# CC3000_WiFi_Shield.net
KiCad netlist of a schematic drawn in EAGLE
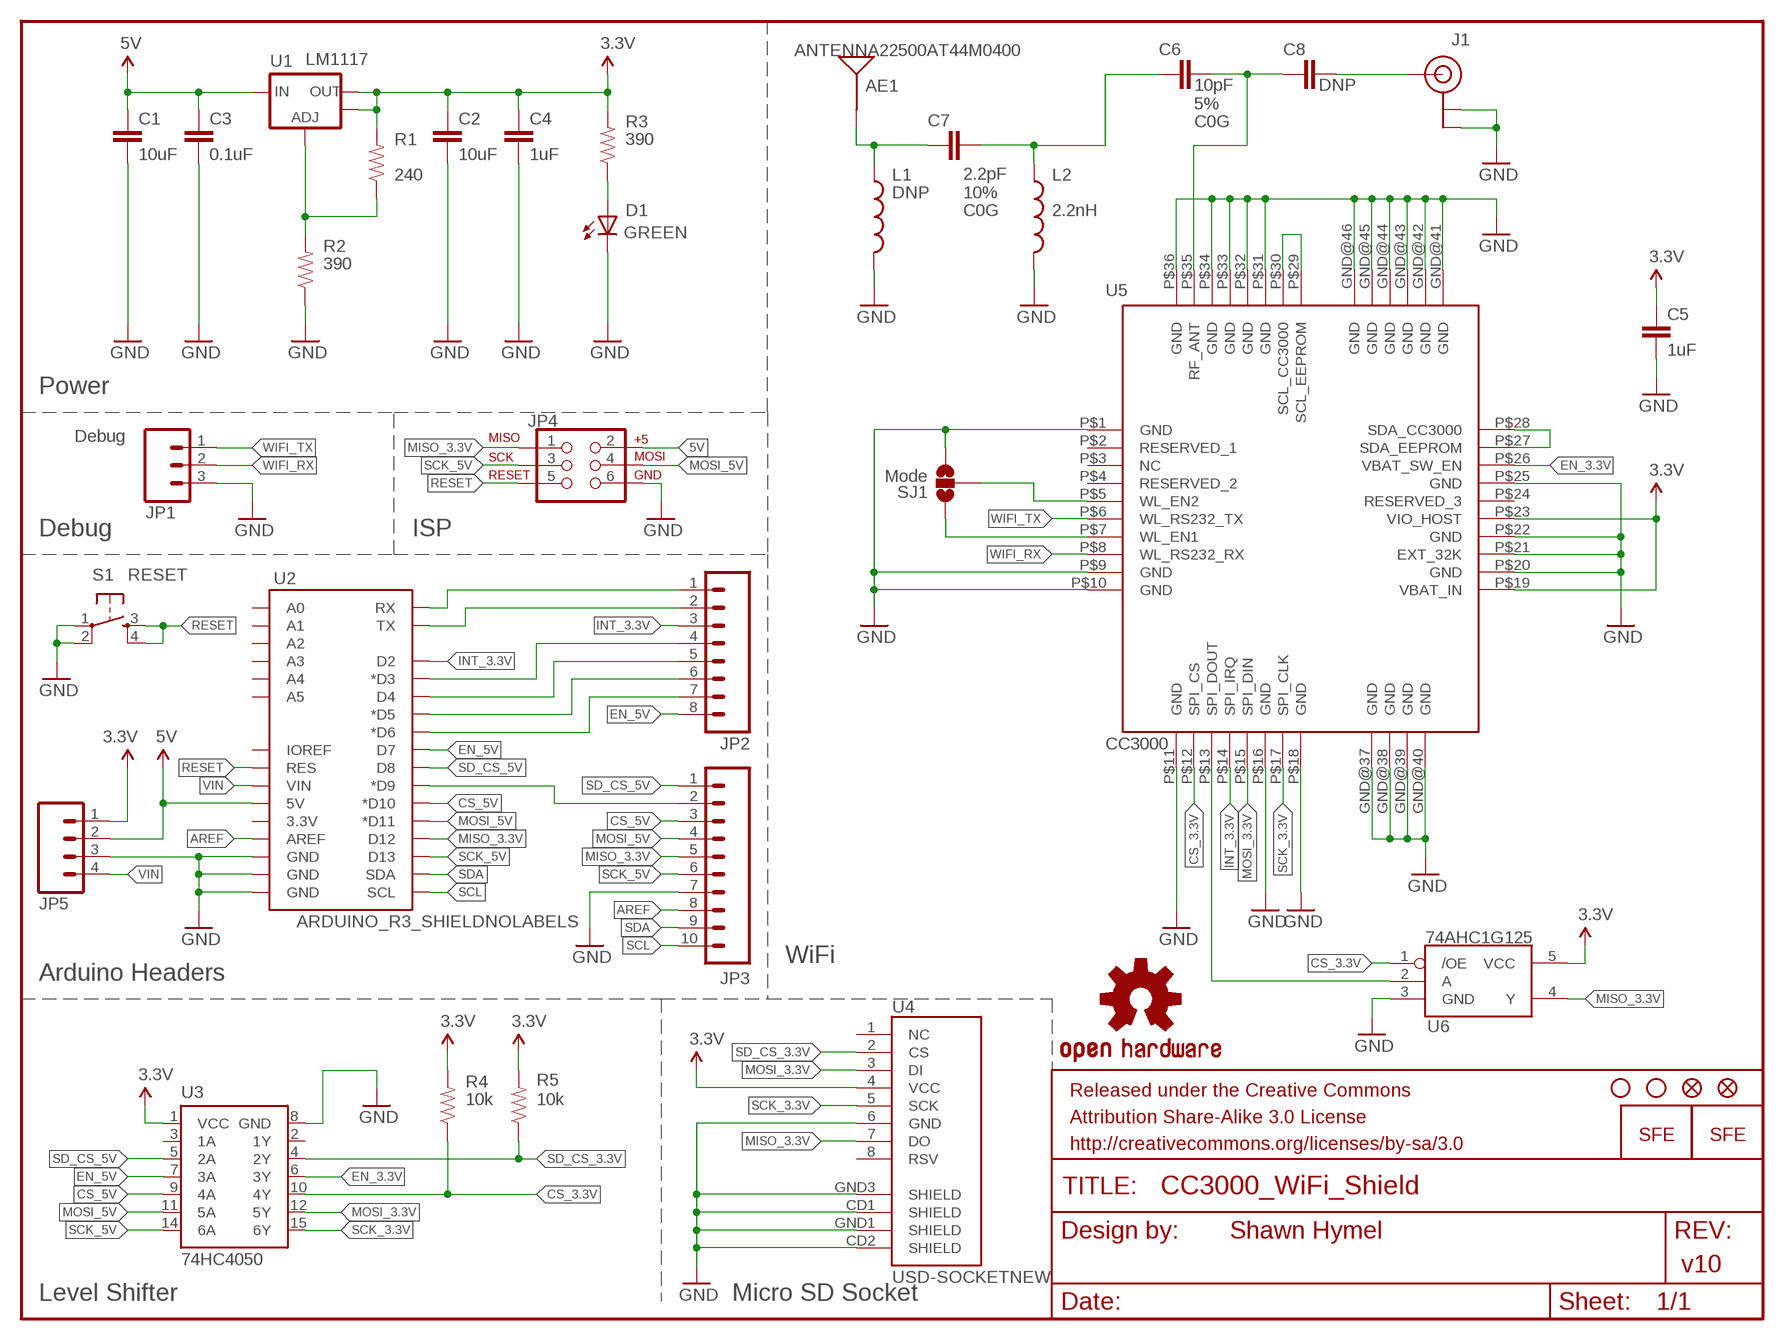
[diagram p0: schematic, sheet 1]

(export (version "E")
  (design (tool "Eeschema 10.0.6"))
  (components
    (comp (ref "AE1")
      (value "ANTENNA22500AT44M0400")
      (footprint "eagle-import:ANTENNA-CHIP_2500AT44M0400")
      (libsource (lib "eagle-import") (part "ANTENNA22500AT44M0400"))
    )
    (comp (ref "C1")
      (value "10uF")
      (footprint "eagle-import:0805")
      (libsource (lib "eagle-import") (part "CAP0805"))
    )
    (comp (ref "C2")
      (value "10uF")
      (footprint "eagle-import:0805")
      (libsource (lib "eagle-import") (part "CAP0805"))
    )
    (comp (ref "C3")
      (value "0.1uF")
      (footprint "eagle-import:0603-CAP")
      (libsource (lib "eagle-import") (part "CAP0603-CAP"))
    )
    (comp (ref "C4")
      (value "1uF")
      (footprint "eagle-import:0805")
      (libsource (lib "eagle-import") (part "CAP0805"))
    )
    (comp (ref "C5")
      (value "1uF")
      (footprint "eagle-import:0805")
      (libsource (lib "eagle-import") (part "CAP0805"))
    )
    (comp (ref "C6")
      (value "10pF")
      (footprint "eagle-import:0603-CAP")
      (fields (field (name "COEFF") "C0G") (field (name "TOL") "5%"))
      (libsource (lib "eagle-import") (part "CAP0603-CAP"))
    )
    (comp (ref "C7")
      (value "2.2pF")
      (footprint "eagle-import:0603-CAP")
      (fields (field (name "COEFF") "C0G") (field (name "TOL") "10%"))
      (libsource (lib "eagle-import") (part "CAP0603-CAP"))
    )
    (comp (ref "C8")
      (value "DNP")
      (footprint "eagle-import:0603-CAP")
      (libsource (lib "eagle-import") (part "CAP0603-CAP"))
    )
    (comp (ref "D1")
      (value "GREEN")
      (footprint "eagle-import:LED-0603")
      (libsource (lib "eagle-import") (part "LED-GREEN0603"))
    )
    (comp (ref "FID1")
      (value "FIDUCIAL1X2")
      (footprint "eagle-import:FIDUCIAL-1X2")
      (libsource (lib "eagle-import") (part "FIDUCIAL1X2"))
    )
    (comp (ref "FID2")
      (value "FIDUCIAL1X2")
      (footprint "eagle-import:FIDUCIAL-1X2")
      (libsource (lib "eagle-import") (part "FIDUCIAL1X2"))
    )
    (comp (ref "FRAME1")
      (value "FRAME-LETTER")
      (footprint "eagle-import:CREATIVE_COMMONS")
      (libsource (lib "eagle-import") (part "FRAME-LETTER"))
    )
    (comp (ref "J1")
      (value "U.FL")
      (footprint "eagle-import:U.FL")
      (libsource (lib "eagle-import") (part "U.FL"))
    )
    (comp (ref "JP1")
      (value "Debug")
      (footprint "eagle-import:1X03")
      (libsource (lib "eagle-import") (part "M03PTH"))
    )
    (comp (ref "JP2")
      (value "M08NO_SILK")
      (footprint "eagle-import:1X08_NO_SILK")
      (libsource (lib "eagle-import") (part "M08NO_SILK"))
    )
    (comp (ref "JP3")
      (value "M10NO_SILK")
      (footprint "eagle-import:1X10_NO_SILK")
      (libsource (lib "eagle-import") (part "M10NO_SILK"))
    )
    (comp (ref "JP4")
      (value "AVR_SPI_PRG_6PTH")
      (footprint "eagle-import:2X3")
      (libsource (lib "eagle-import") (part "AVR_SPI_PRG_6PTH"))
    )
    (comp (ref "JP5")
      (value "M04PTH")
      (footprint "eagle-import:1X04")
      (libsource (lib "eagle-import") (part "M04PTH"))
    )
    (comp (ref "L1")
      (value "DNP")
      (footprint "eagle-import:0603")
      (libsource (lib "eagle-import") (part "INDUCTOR0603"))
    )
    (comp (ref "L2")
      (value "2.2nH")
      (footprint "eagle-import:0603")
      (libsource (lib "eagle-import") (part "INDUCTOR0603"))
    )
    (comp (ref "LOGO1")
      (value "OSHW-LOGOS")
      (footprint "eagle-import:OSHW-LOGO-S")
      (libsource (lib "eagle-import") (part "OSHW-LOGOS"))
    )
    (comp (ref "LOGO2")
      (value "LOGO-SFENEW")
      (footprint "eagle-import:SFE-NEW-WEBLOGO")
      (libsource (lib "eagle-import") (part "LOGO-SFENEW"))
    )
    (comp (ref "LOGO3")
      (value "LOGO-SFESK")
      (footprint "eagle-import:SFE-LOGO-FLAME")
      (libsource (lib "eagle-import") (part "LOGO-SFESK"))
    )
    (comp (ref "R1")
      (value "240")
      (footprint "eagle-import:0603-RES")
      (libsource (lib "eagle-import") (part "RESISTOR0603"))
    )
    (comp (ref "R2")
      (value "390")
      (footprint "eagle-import:0603-RES")
      (libsource (lib "eagle-import") (part "RESISTOR0603"))
    )
    (comp (ref "R3")
      (value "390")
      (footprint "eagle-import:0603-RES")
      (libsource (lib "eagle-import") (part "RESISTOR0603-RES"))
    )
    (comp (ref "R4")
      (value "10k")
      (footprint "eagle-import:0603-RES")
      (libsource (lib "eagle-import") (part "RESISTOR0603-RES"))
    )
    (comp (ref "R5")
      (value "10k")
      (footprint "eagle-import:0603-RES")
      (libsource (lib "eagle-import") (part "RESISTOR0603-RES"))
    )
    (comp (ref "S1")
      (value "RESET")
      (footprint "eagle-import:TACTILE_SWITCH_SMD")
      (libsource (lib "eagle-import") (part "TAC_SWITCHSMD"))
    )
    (comp (ref "SJ1")
      (value "Mode")
      (footprint "eagle-import:SJ_3_PASTE1&2")
      (libsource (lib "eagle-import") (part "SOLDERJUMPER_2WAYPASTE1&2"))
    )
    (comp (ref "STANDOFF1")
      (value "STAND-OFF")
      (footprint "eagle-import:STAND-OFF")
      (libsource (lib "eagle-import") (part "STAND-OFF"))
    )
    (comp (ref "STANDOFF2")
      (value "STAND-OFF")
      (footprint "eagle-import:STAND-OFF")
      (libsource (lib "eagle-import") (part "STAND-OFF"))
    )
    (comp (ref "U1")
      (value "LM1117")
      (footprint "eagle-import:SOT223")
      (libsource (lib "eagle-import") (part "V_REG_LM1117SOT223"))
    )
    (comp (ref "U2")
      (value "ARDUINO_R3_SHIELDNOLABELS")
      (footprint "eagle-import:UNO_R3_SHIELD_NOLABELS")
      (libsource (lib "eagle-import") (part "ARDUINO_R3_SHIELDNOLABELS"))
    )
    (comp (ref "U3")
      (value "74HC4050")
      (footprint "eagle-import:SO016")
      (libsource (lib "eagle-import") (part "HEX_CONVERTER"))
    )
    (comp (ref "U4")
      (value "USD-SOCKETNEW")
      (footprint "eagle-import:MICRO-SD-SOCKET-PP")
      (libsource (lib "eagle-import") (part "USD-SOCKETNEW"))
    )
    (comp (ref "U5")
      (value "CC3000")
      (footprint "eagle-import:QFN-46_CC3000")
      (libsource (lib "eagle-import") (part "CC3000"))
    )
    (comp (ref "U6")
      (value "74AHC1G125")
      (footprint "eagle-import:SOT23-5")
      (libsource (lib "eagle-import") (part "74AHC1G125"))
    )
  )
  (nets
    (net (code "1") (name "3.3V") (class "Default")
      (node (ref "C2") (pin "1") (pinfunction "1_1") (pintype "passive"))
      (node (ref "C4") (pin "1") (pinfunction "1_1") (pintype "passive"))
      (node (ref "C5") (pin "1") (pinfunction "1_1") (pintype "passive"))
      (node (ref "JP5") (pin "1") (pinfunction "1_1") (pintype "passive"))
      (node (ref "R1") (pin "2") (pinfunction "2_2") (pintype "passive"))
      (node (ref "R3") (pin "2") (pinfunction "2_2") (pintype "passive"))
      (node (ref "R4") (pin "2") (pinfunction "2_2") (pintype "passive"))
      (node (ref "R5") (pin "2") (pinfunction "2_2") (pintype "passive"))
      (node (ref "U1") (pin "2") (pinfunction "OUT_2") (pintype "output"))
      (node (ref "U1") (pin "4") (pinfunction "OUT_4") (pintype "output"))
      (node (ref "U3") (pin "1") (pinfunction "VCC_1") (pintype "bidirectional"))
      (node (ref "U4") (pin "4") (pinfunction "VCC_4") (pintype "bidirectional"))
      (node (ref "U5") (pin "P$19") (pinfunction "VBAT_IN_P$19") (pintype "bidirectional"))
      (node (ref "U5") (pin "P$23") (pinfunction "VIO_HOST_P$23") (pintype "bidirectional"))
      (node (ref "U6") (pin "5") (pinfunction "VCC_5") (pintype "bidirectional"))
    )
    (net (code "2") (name "5V") (class "Default")
      (node (ref "C1") (pin "1") (pinfunction "1_1") (pintype "passive"))
      (node (ref "C3") (pin "1") (pinfunction "1_1") (pintype "passive"))
      (node (ref "JP4") (pin "2") (pinfunction "2_2") (pintype "passive"))
      (node (ref "JP5") (pin "2") (pinfunction "2_2") (pintype "passive"))
      (node (ref "U1") (pin "3") (pinfunction "IN_3") (pintype "input"))
      (node (ref "U2") (pin "5V") (pinfunction "5V_5V") (pintype "bidirectional"))
    )
    (net (code "3") (name "AREF") (class "Default")
      (node (ref "JP3") (pin "8") (pinfunction "8_8") (pintype "passive"))
      (node (ref "U2") (pin "AREF") (pinfunction "AREF_AREF") (pintype "bidirectional"))
    )
    (net (code "4") (name "CS_3.3V") (class "Default")
      (node (ref "R4") (pin "1") (pinfunction "1_1") (pintype "passive"))
      (node (ref "U3") (pin "10") (pinfunction "4Y_10") (pintype "bidirectional"))
      (node (ref "U5") (pin "P$12") (pinfunction "SPI_CS_P$12") (pintype "bidirectional"))
      (node (ref "U6") (pin "1") (pinfunction "/OE_1") (pintype "bidirectional"))
    )
    (net (code "5") (name "CS_5V") (class "Default")
      (node (ref "JP3") (pin "3") (pinfunction "3_3") (pintype "passive"))
      (node (ref "U2") (pin "D10") (pinfunction "*D10_D10") (pintype "bidirectional"))
      (node (ref "U3") (pin "9") (pinfunction "4A_9") (pintype "bidirectional"))
    )
    (net (code "6") (name "EN_3.3V") (class "Default")
      (node (ref "U3") (pin "6") (pinfunction "3Y_6") (pintype "bidirectional"))
      (node (ref "U5") (pin "P$26") (pinfunction "VBAT_SW_EN_P$26") (pintype "bidirectional"))
    )
    (net (code "7") (name "EN_5V") (class "Default")
      (node (ref "JP2") (pin "8") (pinfunction "8_8") (pintype "passive"))
      (node (ref "U2") (pin "D7") (pinfunction "D7_D7") (pintype "bidirectional"))
      (node (ref "U3") (pin "7") (pinfunction "3A_7") (pintype "bidirectional"))
    )
    (net (code "8") (name "GND") (class "Default")
      (node (ref "C1") (pin "2") (pinfunction "2_2") (pintype "passive"))
      (node (ref "C2") (pin "2") (pinfunction "2_2") (pintype "passive"))
      (node (ref "C3") (pin "2") (pinfunction "2_2") (pintype "passive"))
      (node (ref "C4") (pin "2") (pinfunction "2_2") (pintype "passive"))
      (node (ref "C5") (pin "2") (pinfunction "2_2") (pintype "passive"))
      (node (ref "D1") (pin "C") (pinfunction "C_C") (pintype "passive"))
      (node (ref "J1") (pin "P$1") (pinfunction "GND_P$1") (pintype "bidirectional"))
      (node (ref "J1") (pin "P$2") (pinfunction "GND_P$2") (pintype "bidirectional"))
      (node (ref "JP1") (pin "3") (pinfunction "3_3") (pintype "passive"))
      (node (ref "JP3") (pin "7") (pinfunction "7_7") (pintype "passive"))
      (node (ref "JP4") (pin "6") (pinfunction "6_6") (pintype "passive"))
      (node (ref "JP5") (pin "3") (pinfunction "3_3") (pintype "passive"))
      (node (ref "L1") (pin "2") (pinfunction "2_2") (pintype "passive"))
      (node (ref "L2") (pin "2") (pinfunction "2_2") (pintype "passive"))
      (node (ref "R2") (pin "1") (pinfunction "1_1") (pintype "passive"))
      (node (ref "S1") (pin "1") (pinfunction "1_1") (pintype "passive"))
      (node (ref "S1") (pin "2") (pinfunction "2_2") (pintype "passive"))
      (node (ref "SJ1") (pin "3") (pinfunction "3_3") (pintype "passive"))
      (node (ref "U2") (pin "GND@0") (pinfunction "GND_GND@0") (pintype "bidirectional"))
      (node (ref "U2") (pin "GND@1") (pinfunction "GND_GND@1") (pintype "bidirectional"))
      (node (ref "U2") (pin "GND@2") (pinfunction "GND_GND@2") (pintype "bidirectional"))
      (node (ref "U3") (pin "8") (pinfunction "GND_8") (pintype "bidirectional"))
      (node (ref "U4") (pin "6") (pinfunction "GND_6") (pintype "bidirectional"))
      (node (ref "U4") (pin "CD1") (pinfunction "SHIELD_CD1") (pintype "bidirectional"))
      (node (ref "U4") (pin "CD2") (pinfunction "SHIELD_CD2") (pintype "bidirectional"))
      (node (ref "U4") (pin "GND1") (pinfunction "SHIELD_GND1") (pintype "bidirectional"))
      (node (ref "U4") (pin "GND3") (pinfunction "SHIELD_GND3") (pintype "bidirectional"))
      (node (ref "U5") (pin "GND@37") (pinfunction "GND_GND@37") (pintype "bidirectional"))
      (node (ref "U5") (pin "GND@38") (pinfunction "GND_GND@38") (pintype "bidirectional"))
      (node (ref "U5") (pin "GND@39") (pinfunction "GND_GND@39") (pintype "bidirectional"))
      (node (ref "U5") (pin "GND@40") (pinfunction "GND_GND@40") (pintype "bidirectional"))
      (node (ref "U5") (pin "GND@41") (pinfunction "GND_GND@41") (pintype "bidirectional"))
      (node (ref "U5") (pin "GND@42") (pinfunction "GND_GND@42") (pintype "bidirectional"))
      (node (ref "U5") (pin "GND@43") (pinfunction "GND_GND@43") (pintype "bidirectional"))
      (node (ref "U5") (pin "GND@44") (pinfunction "GND_GND@44") (pintype "bidirectional"))
      (node (ref "U5") (pin "GND@45") (pinfunction "GND_GND@45") (pintype "bidirectional"))
      (node (ref "U5") (pin "GND@46") (pinfunction "GND_GND@46") (pintype "bidirectional"))
      (node (ref "U5") (pin "P$1") (pinfunction "GND_P$1") (pintype "bidirectional"))
      (node (ref "U5") (pin "P$10") (pinfunction "GND_P$10") (pintype "bidirectional"))
      (node (ref "U5") (pin "P$11") (pinfunction "GND_P$11") (pintype "bidirectional"))
      (node (ref "U5") (pin "P$16") (pinfunction "GND_P$16") (pintype "bidirectional"))
      (node (ref "U5") (pin "P$18") (pinfunction "GND_P$18") (pintype "bidirectional"))
      (node (ref "U5") (pin "P$20") (pinfunction "GND_P$20") (pintype "bidirectional"))
      (node (ref "U5") (pin "P$21") (pinfunction "EXT_32K_P$21") (pintype "bidirectional"))
      (node (ref "U5") (pin "P$22") (pinfunction "GND_P$22") (pintype "bidirectional"))
      (node (ref "U5") (pin "P$25") (pinfunction "GND_P$25") (pintype "bidirectional"))
      (node (ref "U5") (pin "P$31") (pinfunction "GND_P$31") (pintype "bidirectional"))
      (node (ref "U5") (pin "P$32") (pinfunction "GND_P$32") (pintype "bidirectional"))
      (node (ref "U5") (pin "P$33") (pinfunction "GND_P$33") (pintype "bidirectional"))
      (node (ref "U5") (pin "P$34") (pinfunction "GND_P$34") (pintype "bidirectional"))
      (node (ref "U5") (pin "P$36") (pinfunction "GND_P$36") (pintype "bidirectional"))
      (node (ref "U5") (pin "P$9") (pinfunction "GND_P$9") (pintype "bidirectional"))
      (node (ref "U6") (pin "3") (pinfunction "GND_3") (pintype "bidirectional"))
    )
    (net (code "9") (name "INT_3.3V") (class "Default")
      (node (ref "JP2") (pin "3") (pinfunction "3_3") (pintype "passive"))
      (node (ref "U2") (pin "D2") (pinfunction "D2_D2") (pintype "bidirectional"))
      (node (ref "U5") (pin "P$14") (pinfunction "SPI_IRQ_P$14") (pintype "bidirectional"))
    )
    (net (code "10") (name "MISO_3.3V") (class "Default")
      (node (ref "JP3") (pin "5") (pinfunction "5_5") (pintype "passive"))
      (node (ref "JP4") (pin "1") (pinfunction "1_1") (pintype "passive"))
      (node (ref "U2") (pin "D12") (pinfunction "D12_D12") (pintype "bidirectional"))
      (node (ref "U4") (pin "7") (pinfunction "DO_7") (pintype "bidirectional"))
      (node (ref "U6") (pin "4") (pinfunction "Y_4") (pintype "bidirectional"))
    )
    (net (code "11") (name "MOSI_3.3V") (class "Default")
      (node (ref "U3") (pin "12") (pinfunction "5Y_12") (pintype "bidirectional"))
      (node (ref "U4") (pin "3") (pinfunction "DI_3") (pintype "bidirectional"))
      (node (ref "U5") (pin "P$15") (pinfunction "SPI_DIN_P$15") (pintype "bidirectional"))
    )
    (net (code "12") (name "MOSI_5V") (class "Default")
      (node (ref "JP3") (pin "4") (pinfunction "4_4") (pintype "passive"))
      (node (ref "JP4") (pin "4") (pinfunction "4_4") (pintype "passive"))
      (node (ref "U2") (pin "D11") (pinfunction "*D11_D11") (pintype "bidirectional"))
      (node (ref "U3") (pin "11") (pinfunction "5A_11") (pintype "bidirectional"))
    )
    (net (code "13") (name "Net-(AE1-SIGNAL)") (class "Default")
      (node (ref "AE1") (pin "FEED") (pinfunction "SIGNAL_FEED") (pintype "bidirectional"))
      (node (ref "C7") (pin "1") (pinfunction "1_1") (pintype "passive"))
      (node (ref "L1") (pin "1") (pinfunction "1_1") (pintype "passive"))
    )
    (net (code "14") (name "Net-(C6-Pad1)") (class "Default")
      (node (ref "C6") (pin "1") (pinfunction "1_1") (pintype "passive"))
      (node (ref "C7") (pin "2") (pinfunction "2_2") (pintype "passive"))
      (node (ref "L2") (pin "1") (pinfunction "1_1") (pintype "passive"))
    )
    (net (code "15") (name "Net-(D1-PadA)") (class "Default")
      (node (ref "D1") (pin "A") (pinfunction "A_A") (pintype "passive"))
      (node (ref "R3") (pin "1") (pinfunction "1_1") (pintype "passive"))
    )
    (net (code "16") (name "Net-(J1-SIGNAL)") (class "Default")
      (node (ref "C8") (pin "2") (pinfunction "2_2") (pintype "passive"))
      (node (ref "J1") (pin "P$3") (pinfunction "SIGNAL_P$3") (pintype "bidirectional"))
    )
    (net (code "17") (name "Net-(JP2-Pad1)") (class "Default")
      (node (ref "JP2") (pin "1") (pinfunction "1_1") (pintype "passive"))
      (node (ref "U2") (pin "RX") (pinfunction "RX_RX") (pintype "bidirectional"))
    )
    (net (code "18") (name "Net-(JP2-Pad2)") (class "Default")
      (node (ref "JP2") (pin "2") (pinfunction "2_2") (pintype "passive"))
      (node (ref "U2") (pin "TX") (pinfunction "TX_TX") (pintype "bidirectional"))
    )
    (net (code "19") (name "Net-(JP2-Pad5)") (class "Default")
      (node (ref "JP2") (pin "5") (pinfunction "5_5") (pintype "passive"))
      (node (ref "U2") (pin "D4") (pinfunction "D4_D4") (pintype "bidirectional"))
    )
    (net (code "20") (name "Net-(U1-ADJ)") (class "Default")
      (node (ref "R1") (pin "1") (pinfunction "1_1") (pintype "passive"))
      (node (ref "R2") (pin "2") (pinfunction "2_2") (pintype "passive"))
      (node (ref "U1") (pin "1") (pinfunction "ADJ_1") (pintype "input"))
    )
    (net (code "21") (name "Net-(U2-*D3)") (class "Default")
      (node (ref "JP2") (pin "4") (pinfunction "4_4") (pintype "passive"))
      (node (ref "U2") (pin "D3") (pinfunction "*D3_D3") (pintype "bidirectional"))
    )
    (net (code "22") (name "Net-(U2-*D5)") (class "Default")
      (node (ref "JP2") (pin "6") (pinfunction "6_6") (pintype "passive"))
      (node (ref "U2") (pin "D5") (pinfunction "*D5_D5") (pintype "bidirectional"))
    )
    (net (code "23") (name "Net-(U2-*D6)") (class "Default")
      (node (ref "JP2") (pin "7") (pinfunction "7_7") (pintype "passive"))
      (node (ref "U2") (pin "D6") (pinfunction "*D6_D6") (pintype "bidirectional"))
    )
    (net (code "24") (name "Net-(U2-*D9)") (class "Default")
      (node (ref "JP3") (pin "2") (pinfunction "2_2") (pintype "passive"))
      (node (ref "U2") (pin "D9") (pinfunction "*D9_D9") (pintype "bidirectional"))
    )
    (net (code "25") (name "Net-(U5-RF_ANT)") (class "Default")
      (node (ref "C6") (pin "2") (pinfunction "2_2") (pintype "passive"))
      (node (ref "C8") (pin "1") (pinfunction "1_1") (pintype "passive"))
      (node (ref "U5") (pin "P$35") (pinfunction "RF_ANT_P$35") (pintype "bidirectional"))
    )
    (net (code "26") (name "Net-(U5-SCL_CC3000)") (class "Default")
      (node (ref "U5") (pin "P$29") (pinfunction "SCL_EEPROM_P$29") (pintype "bidirectional"))
      (node (ref "U5") (pin "P$30") (pinfunction "SCL_CC3000_P$30") (pintype "bidirectional"))
    )
    (net (code "27") (name "Net-(U5-SDA_CC3000)") (class "Default")
      (node (ref "U5") (pin "P$27") (pinfunction "SDA_EEPROM_P$27") (pintype "bidirectional"))
      (node (ref "U5") (pin "P$28") (pinfunction "SDA_CC3000_P$28") (pintype "bidirectional"))
    )
    (net (code "28") (name "Net-(U5-SPI_DOUT)") (class "Default")
      (node (ref "U5") (pin "P$13") (pinfunction "SPI_DOUT_P$13") (pintype "bidirectional"))
      (node (ref "U6") (pin "2") (pinfunction "A_2") (pintype "bidirectional"))
    )
    (net (code "29") (name "Net-(U5-WL_EN1)") (class "Default")
      (node (ref "SJ1") (pin "1") (pinfunction "1_1") (pintype "passive"))
      (node (ref "U5") (pin "P$7") (pinfunction "WL_EN1_P$7") (pintype "bidirectional"))
    )
    (net (code "30") (name "Net-(U5-WL_EN2)") (class "Default")
      (node (ref "SJ1") (pin "2") (pinfunction "2_2") (pintype "passive"))
      (node (ref "U5") (pin "P$5") (pinfunction "WL_EN2_P$5") (pintype "bidirectional"))
    )
    (net (code "31") (name "RESET") (class "Default")
      (node (ref "JP4") (pin "5") (pinfunction "5_5") (pintype "passive"))
      (node (ref "S1") (pin "3") (pinfunction "3_3") (pintype "passive"))
      (node (ref "S1") (pin "4") (pinfunction "4_4") (pintype "passive"))
      (node (ref "U2") (pin "RES") (pinfunction "RES_RES") (pintype "bidirectional"))
    )
    (net (code "32") (name "SCK_3.3V") (class "Default")
      (node (ref "U3") (pin "15") (pinfunction "6Y_15") (pintype "bidirectional"))
      (node (ref "U4") (pin "5") (pinfunction "SCK_5") (pintype "bidirectional"))
      (node (ref "U5") (pin "P$17") (pinfunction "SPI_CLK_P$17") (pintype "bidirectional"))
    )
    (net (code "33") (name "SCK_5V") (class "Default")
      (node (ref "JP3") (pin "6") (pinfunction "6_6") (pintype "passive"))
      (node (ref "JP4") (pin "3") (pinfunction "3_3") (pintype "passive"))
      (node (ref "U2") (pin "D13") (pinfunction "D13_D13") (pintype "bidirectional"))
      (node (ref "U3") (pin "14") (pinfunction "6A_14") (pintype "bidirectional"))
    )
    (net (code "34") (name "SCL") (class "Default")
      (node (ref "JP3") (pin "10") (pinfunction "10_10") (pintype "passive"))
      (node (ref "U2") (pin "SCL") (pinfunction "SCL_SCL") (pintype "bidirectional"))
    )
    (net (code "35") (name "SDA") (class "Default")
      (node (ref "JP3") (pin "9") (pinfunction "9_9") (pintype "passive"))
      (node (ref "U2") (pin "SDA") (pinfunction "SDA_SDA") (pintype "bidirectional"))
    )
    (net (code "36") (name "SD_CS_3.3V") (class "Default")
      (node (ref "R5") (pin "1") (pinfunction "1_1") (pintype "passive"))
      (node (ref "U3") (pin "4") (pinfunction "2Y_4") (pintype "bidirectional"))
      (node (ref "U4") (pin "2") (pinfunction "CS_2") (pintype "bidirectional"))
    )
    (net (code "37") (name "SD_CS_5V") (class "Default")
      (node (ref "JP3") (pin "1") (pinfunction "1_1") (pintype "passive"))
      (node (ref "U2") (pin "D8") (pinfunction "D8_D8") (pintype "bidirectional"))
      (node (ref "U3") (pin "5") (pinfunction "2A_5") (pintype "bidirectional"))
    )
    (net (code "38") (name "VIN") (class "Default")
      (node (ref "JP5") (pin "4") (pinfunction "4_4") (pintype "passive"))
      (node (ref "U2") (pin "VIN") (pinfunction "VIN_VIN") (pintype "bidirectional"))
    )
    (net (code "39") (name "WIFI_RX") (class "Default")
      (node (ref "JP1") (pin "2") (pinfunction "2_2") (pintype "passive"))
      (node (ref "U5") (pin "P$8") (pinfunction "WL_RS232_RX_P$8") (pintype "bidirectional"))
    )
    (net (code "40") (name "WIFI_TX") (class "Default")
      (node (ref "JP1") (pin "1") (pinfunction "1_1") (pintype "passive"))
      (node (ref "U5") (pin "P$6") (pinfunction "WL_RS232_TX_P$6") (pintype "bidirectional"))
    )
    (net (code "41") (name "unconnected-(U2-Pad3.3V)") (class "Default")
      (node (ref "U2") (pin "3.3V") (pinfunction "3.3V_3.3V") (pintype "bidirectional"))
    )
    (net (code "42") (name "unconnected-(U2-PadA0)") (class "Default")
      (node (ref "U2") (pin "A0") (pinfunction "A0_A0") (pintype "bidirectional"))
    )
    (net (code "43") (name "unconnected-(U2-PadA1)") (class "Default")
      (node (ref "U2") (pin "A1") (pinfunction "A1_A1") (pintype "bidirectional"))
    )
    (net (code "44") (name "unconnected-(U2-PadA2)") (class "Default")
      (node (ref "U2") (pin "A2") (pinfunction "A2_A2") (pintype "bidirectional"))
    )
    (net (code "45") (name "unconnected-(U2-PadA3)") (class "Default")
      (node (ref "U2") (pin "A3") (pinfunction "A3_A3") (pintype "bidirectional"))
    )
    (net (code "46") (name "unconnected-(U2-PadA4)") (class "Default")
      (node (ref "U2") (pin "A4") (pinfunction "A4_A4") (pintype "bidirectional"))
    )
    (net (code "47") (name "unconnected-(U2-PadA5)") (class "Default")
      (node (ref "U2") (pin "A5") (pinfunction "A5_A5") (pintype "bidirectional"))
    )
    (net (code "48") (name "unconnected-(U2-PadIOREF)") (class "Default")
      (node (ref "U2") (pin "IOREF") (pinfunction "IOREF_IOREF") (pintype "bidirectional"))
    )
    (net (code "49") (name "unconnected-(U3-1A-Pad3)") (class "Default")
      (node (ref "U3") (pin "3") (pinfunction "1A_3") (pintype "bidirectional"))
    )
    (net (code "50") (name "unconnected-(U3-1Y-Pad2)") (class "Default")
      (node (ref "U3") (pin "2") (pinfunction "1Y_2") (pintype "bidirectional"))
    )
    (net (code "51") (name "unconnected-(U4-NC-Pad1)") (class "Default")
      (node (ref "U4") (pin "1") (pinfunction "NC_1") (pintype "bidirectional"))
    )
    (net (code "52") (name "unconnected-(U4-RSV-Pad8)") (class "Default")
      (node (ref "U4") (pin "8") (pinfunction "RSV_8") (pintype "bidirectional"))
    )
    (net (code "53") (name "unconnected-(U5-NC-PadP$3)") (class "Default")
      (node (ref "U5") (pin "P$3") (pinfunction "NC_P$3") (pintype "bidirectional"))
    )
    (net (code "54") (name "unconnected-(U5-RESERVED_1-PadP$2)") (class "Default")
      (node (ref "U5") (pin "P$2") (pinfunction "RESERVED_1_P$2") (pintype "bidirectional"))
    )
    (net (code "55") (name "unconnected-(U5-RESERVED_2-PadP$4)") (class "Default")
      (node (ref "U5") (pin "P$4") (pinfunction "RESERVED_2_P$4") (pintype "bidirectional"))
    )
    (net (code "56") (name "unconnected-(U5-RESERVED_3-PadP$24)") (class "Default")
      (node (ref "U5") (pin "P$24") (pinfunction "RESERVED_3_P$24") (pintype "bidirectional"))
    )
  )
)
